# SAMV71_Xplained_Ultra_Memory.net
KiCad netlist of a schematic drawn in Altium Designer
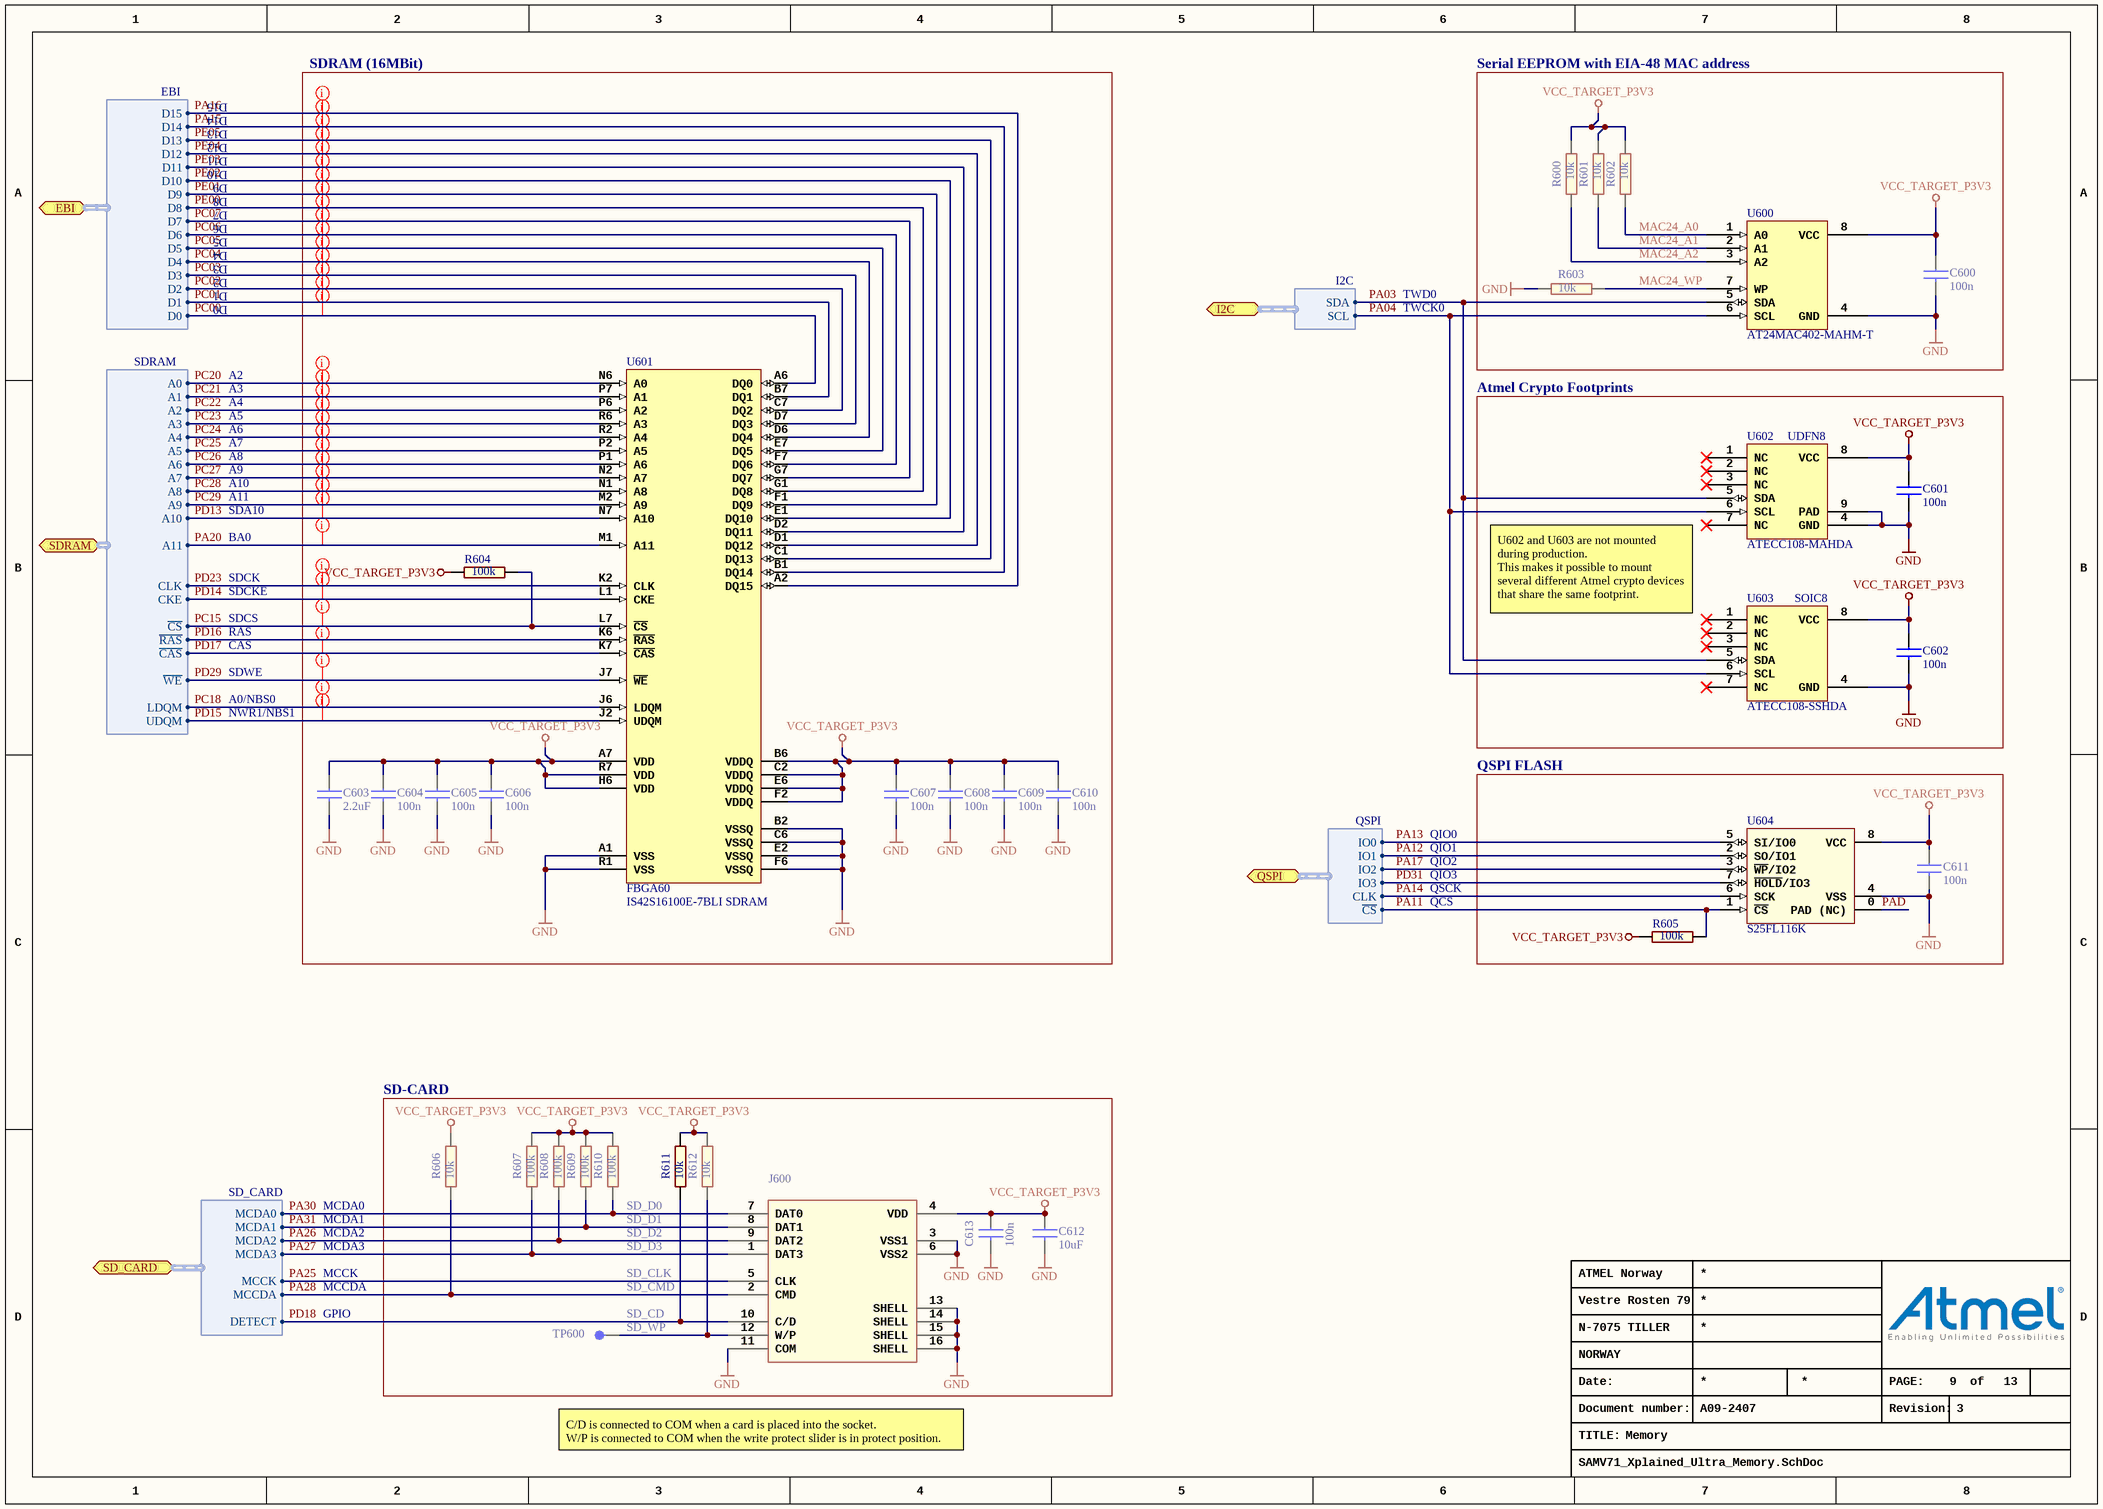
[diagram p0: SAMV71_Xplained_Ultra_Memory.SchDoc]

(export (version "E")
  (design (tool "Eeschema 10.0.6"))
  (components
    (comp (ref "C600")
      (value "100n")
      (footprint "AP1-00001")
      (description "Ceramic capacitor, SMD 0402, X7R, 16V, +/-10%")
      (fields (field (name "TOLERANCE") "16V, +/-10%") (field (name "MANUFACTURER") "Kemet"))
      (libsource (lib "AltiumDbLib") (part "CAP-NONPOL"))
    )
    (comp (ref "C601")
      (value "100n")
      (footprint "AP1-00001")
      (description "Ceramic capacitor, SMD 0402, X7R, 16V, +/-10%")
      (fields (field (name "TOLERANCE") "16V, +/-10%") (field (name "MANUFACTURER") "Kemet"))
      (libsource (lib "AltiumDbLib") (part "CAP-NONPOL"))
    )
    (comp (ref "C602")
      (value "100n")
      (footprint "AP1-00001")
      (description "Ceramic capacitor, SMD 0402, X7R, 16V, +/-10%")
      (fields (field (name "TOLERANCE") "16V, +/-10%") (field (name "MANUFACTURER") "Kemet"))
      (libsource (lib "AltiumDbLib") (part "CAP-NONPOL"))
    )
    (comp (ref "C603")
      (value "2.2uF")
      (footprint "AP1-00053")
      (description "Ceramic capacitor, SMD 0402, X5R, 6.3V, +/-20%")
      (fields (field (name "TOLERANCE") "Â±20%") (field (name "MANUFACTURER") "Kemet"))
      (libsource (lib "AltiumDbLib") (part "CAP-NONPOL"))
    )
    (comp (ref "C604")
      (value "100n")
      (footprint "AP1-00053")
      (description "Ceramic capacitor, SMD 0402, X7R, 16V, +/-10%")
      (fields (field (name "TOLERANCE") "16V, +/-10%") (field (name "MANUFACTURER") "Kemet"))
      (libsource (lib "AltiumDbLib") (part "CAP-NONPOL"))
    )
    (comp (ref "C605")
      (value "100n")
      (footprint "AP1-00053")
      (description "Ceramic capacitor, SMD 0402, X7R, 16V, +/-10%")
      (fields (field (name "TOLERANCE") "16V, +/-10%") (field (name "MANUFACTURER") "Kemet"))
      (libsource (lib "AltiumDbLib") (part "CAP-NONPOL"))
    )
    (comp (ref "C606")
      (value "100n")
      (footprint "AP1-00053")
      (description "Ceramic capacitor, SMD 0402, X7R, 16V, +/-10%")
      (fields (field (name "TOLERANCE") "16V, +/-10%") (field (name "MANUFACTURER") "Kemet"))
      (libsource (lib "AltiumDbLib") (part "CAP-NONPOL"))
    )
    (comp (ref "C607")
      (value "100n")
      (footprint "AP1-00053")
      (description "Ceramic capacitor, SMD 0402, X7R, 16V, +/-10%")
      (fields (field (name "TOLERANCE") "16V, +/-10%") (field (name "MANUFACTURER") "Kemet"))
      (libsource (lib "AltiumDbLib") (part "CAP-NONPOL"))
    )
    (comp (ref "C608")
      (value "100n")
      (footprint "AP1-00053")
      (description "Ceramic capacitor, SMD 0402, X7R, 16V, +/-10%")
      (fields (field (name "TOLERANCE") "16V, +/-10%") (field (name "MANUFACTURER") "Kemet"))
      (libsource (lib "AltiumDbLib") (part "CAP-NONPOL"))
    )
    (comp (ref "C609")
      (value "100n")
      (footprint "AP1-00053")
      (description "Ceramic capacitor, SMD 0402, X7R, 16V, +/-10%")
      (fields (field (name "TOLERANCE") "16V, +/-10%") (field (name "MANUFACTURER") "Kemet"))
      (libsource (lib "AltiumDbLib") (part "CAP-NONPOL"))
    )
    (comp (ref "C610")
      (value "100n")
      (footprint "AP1-00053")
      (description "Ceramic capacitor, SMD 0402, X7R, 16V, +/-10%")
      (fields (field (name "TOLERANCE") "16V, +/-10%") (field (name "MANUFACTURER") "Kemet"))
      (libsource (lib "AltiumDbLib") (part "CAP-NONPOL"))
    )
    (comp (ref "C611")
      (value "100n")
      (footprint "AP1-00001")
      (description "Ceramic capacitor, SMD 0402, X7R, 16V, +/-10%")
      (fields (field (name "TOLERANCE") "16V, +/-10%") (field (name "MANUFACTURER") "Kemet"))
      (libsource (lib "AltiumDbLib") (part "CAP-NONPOL"))
    )
    (comp (ref "C612")
      (value "10uF")
      (footprint "AP1-00041")
      (description "Ceramic capacitor, SMD 0805, X5R, 10V, 10 %, (de19441)")
      (fields (field (name "TOLERANCE") "10%") (field (name "MANUFACTURER") "Murata"))
      (libsource (lib "AltiumDbLib") (part "CAP-NONPOL"))
    )
    (comp (ref "C613")
      (value "100n")
      (footprint "AP1-00001")
      (description "Ceramic capacitor, SMD 0402, X7R, 16V, +/-10%")
      (fields (field (name "TOLERANCE") "16V, +/-10%") (field (name "MANUFACTURER") "Kemet"))
      (libsource (lib "AltiumDbLib") (part "CAP-NONPOL"))
    )
    (comp (ref "J600")
      (value "~")
      (footprint "AP8-00377")
      (description "SD/MMC socket, 2.7mm, push-push, SMD")
      (fields
        (field (name "MANUFACTURER") "Kyocera-elco")
        (field (name "MPN") "KYOCERA - 14 5738 009 220 859+")
      )
      (libsource (lib "AltiumDbLib") (part "SD_MMC"))
    )
    (comp (ref "R600")
      (value "10k")
      (footprint "AP2-00000")
      (description "Thick film resistor, SMD 0402, 1/16W, 1%")
      (fields (field (name "TOLERANCE") "1 %") (field (name "MANUFACTURER") "vishay"))
      (libsource (lib "AltiumDbLib") (part "R2"))
    )
    (comp (ref "R601")
      (value "10k")
      (footprint "AP2-00000")
      (description "Thick film resistor, SMD 0402, 1/16W, 1%")
      (fields (field (name "TOLERANCE") "1 %") (field (name "MANUFACTURER") "vishay"))
      (libsource (lib "AltiumDbLib") (part "R2"))
    )
    (comp (ref "R602")
      (value "10k")
      (footprint "AP2-00000")
      (description "Thick film resistor, SMD 0402, 1/16W, 1%")
      (fields (field (name "TOLERANCE") "1 %") (field (name "MANUFACTURER") "vishay"))
      (libsource (lib "AltiumDbLib") (part "R2"))
    )
    (comp (ref "R603")
      (value "10k")
      (footprint "AP2-00000")
      (description "Thick film resistor, SMD 0402, 1/16W, 1%")
      (fields (field (name "TOLERANCE") "1 %") (field (name "MANUFACTURER") "vishay"))
      (libsource (lib "") (part "R2_1"))
    )
    (comp (ref "R604")
      (value "100k")
      (footprint "AP2-00000")
      (description "Thick film resistor, SMD 0402, 1/16W, 1%")
      (fields (field (name "TOLERANCE") "1 %"))
      (libsource (lib "") (part "R2_1"))
    )
    (comp (ref "R605")
      (value "100k")
      (footprint "AP2-00000")
      (description "Thick film resistor, SMD 0402, 1/16W, 1%")
      (fields (field (name "TOLERANCE") "1 %"))
      (libsource (lib "") (part "R2_1"))
    )
    (comp (ref "R606")
      (value "10k")
      (footprint "AP2-00000")
      (description "Thick film resistor, SMD 0402, 1/16W, 1%")
      (fields (field (name "TOLERANCE") "1 %") (field (name "MANUFACTURER") "vishay"))
      (libsource (lib "AltiumDbLib") (part "R2"))
    )
    (comp (ref "R607")
      (value "100k")
      (footprint "AP2-00000")
      (description "Thick film resistor, SMD 0402, 1/16W, 1%")
      (fields (field (name "TOLERANCE") "1 %"))
      (libsource (lib "AltiumDbLib") (part "R2"))
    )
    (comp (ref "R608")
      (value "100k")
      (footprint "AP2-00000")
      (description "Thick film resistor, SMD 0402, 1/16W, 1%")
      (fields (field (name "TOLERANCE") "1 %"))
      (libsource (lib "AltiumDbLib") (part "R2"))
    )
    (comp (ref "R609")
      (value "100k")
      (footprint "AP2-00000")
      (description "Thick film resistor, SMD 0402, 1/16W, 1%")
      (fields (field (name "TOLERANCE") "1 %"))
      (libsource (lib "AltiumDbLib") (part "R2"))
    )
    (comp (ref "R610")
      (value "100k")
      (footprint "AP2-00000")
      (description "Thick film resistor, SMD 0402, 1/16W, 1%")
      (fields (field (name "TOLERANCE") "1 %"))
      (libsource (lib "AltiumDbLib") (part "R2"))
    )
    (comp (ref "R611")
      (value "10k")
      (footprint "AP2-00000")
      (description "Thick film resistor, SMD 0402, 1/16W, 1%")
      (fields (field (name "TOLERANCE") "1 %") (field (name "MANUFACTURER") "vishay"))
      (libsource (lib "AltiumDbLib") (part "R2"))
    )
    (comp (ref "R612")
      (value "10k")
      (footprint "AP2-00000")
      (description "Thick film resistor, SMD 0402, 1/16W, 1%")
      (fields (field (name "TOLERANCE") "1 %") (field (name "MANUFACTURER") "vishay"))
      (libsource (lib "AltiumDbLib") (part "R2"))
    )
    (comp (ref "TP600")
      (value "~")
      (footprint "AP8-00010")
      (description "Single SMD testpad")
      (libsource (lib "AltiumDbLib") (part "TESTPOINT"))
    )
    (comp (ref "U600")
      (value "AT24MAC402-MAHM-T")
      (footprint "AP6-00186")
      (description "2kbit I2C EEPROM, single EUI-48 MAC, 1.7-5.5V, 2x3mm UDFN (8MA2)")
      (fields (field (name "MANUFACTURER") "ATMEL"))
      (libsource (lib "AltiumDbLib") (part "AT24MAC-8PIN"))
    )
    (comp (ref "U601")
      (value "FBGA60")
      (footprint "AP6-00400")
      (description "16Mbit  SDRAM (512K Words x 16 Bits x 2 Banks), 143 MHz 3,3V")
      (fields
        (field (name "ALTIUM_VALUE") "IS42S16100E-7BLI SDRAM")
        (field (name "MANUFACTURER") "ISSI")
        (field (name "MPN") "IS42S16100E-7BLI")
      )
      (libsource (lib "AltiumDbLib") (part "IS42S16100E"))
    )
    (comp (ref "U602")
      (value "ATECC108-MAHDA")
      (footprint "AP6-00409")
      (description "Secure authentication and product validation device, EEPROM, I2C, 2.0 - 5.5V, UDFN8")
      (fields (field (name "MANUFACTURER") "ATMEL") (field (name "MPN") "ATECC108-MAHDA-T"))
      (libsource (lib "AltiumDbLib") (part "ATECC108_UDFN"))
    )
    (comp (ref "U603")
      (value "ATECC108-SSHDA")
      (footprint "AP6-00071")
      (description "Secure authentication and product validation device, EEPROM, I2C, 2.0 - 5.5V, SOIC8")
      (fields (field (name "MANUFACTURER") "ATMEL") (field (name "MPN") "ATECC108-SSHDA-T"))
      (libsource (lib "AltiumDbLib") (part "ATECC108_SOIC"))
    )
    (comp (ref "U604")
      (value "S25FL116K")
      (footprint "AP6-00402")
      (description "16 Mbit (2MB) SPI Quad I/O flash, 3.3V, 108MHz, WSON-8, industrial temperature")
      (fields (field (name "MANUFACTURER") "Spansion") (field (name "MPN") "S25FL116K0XNFI013"))
      (libsource (lib "AltiumDbLib") (part "S25FL1"))
    )
  )
  (nets
    (net (code "6") (name "/MAC24_A0") (class "Default")
      (node (ref "R602") (pin "1") (pinfunction "1_1") (pintype "passive"))
      (node (ref "U600") (pin "1") (pinfunction "A0_1") (pintype "input"))
    )
    (net (code "7") (name "/MAC24_A1") (class "Default")
      (node (ref "R601") (pin "1") (pinfunction "1_1") (pintype "passive"))
      (node (ref "U600") (pin "2") (pinfunction "A1_2") (pintype "input"))
    )
    (net (code "8") (name "/MAC24_A2") (class "Default")
      (node (ref "R600") (pin "1") (pinfunction "1_1") (pintype "passive"))
      (node (ref "U600") (pin "3") (pinfunction "A2_3") (pintype "input"))
    )
    (net (code "9") (name "/MAC24_WP") (class "Default")
      (node (ref "R603") (pin "2") (pinfunction "2_2") (pintype "passive"))
      (node (ref "U600") (pin "7") (pinfunction "WP_7") (pintype "input"))
    )
    (net (code "10") (name "/PA03") (class "Default")
      (node (ref "U600") (pin "5") (pinfunction "SDA_5") (pintype "bidirectional"))
      (node (ref "U602") (pin "5") (pinfunction "SDA_5") (pintype "bidirectional"))
      (node (ref "U603") (pin "5") (pinfunction "SDA_5") (pintype "bidirectional"))
    )
    (net (code "11") (name "/PA04") (class "Default")
      (node (ref "U600") (pin "6") (pinfunction "SCL_6") (pintype "input"))
      (node (ref "U602") (pin "6") (pinfunction "SCL_6") (pintype "input"))
      (node (ref "U603") (pin "6") (pinfunction "SCL_6") (pintype "input"))
    )
    (net (code "12") (name "/PA11") (class "Default")
      (node (ref "R605") (pin "2") (pinfunction "2_2") (pintype "passive"))
      (node (ref "U604") (pin "1") (pinfunction "~{CS}_1") (pintype "input"))
    )
    (net (code "13") (name "/PA12") (class "Default")
      (node (ref "U604") (pin "2") (pinfunction "SO/IO1_2") (pintype "bidirectional"))
    )
    (net (code "14") (name "/PA13") (class "Default")
      (node (ref "U604") (pin "5") (pinfunction "SI/IO0_5") (pintype "bidirectional"))
    )
    (net (code "15") (name "/PA14") (class "Default")
      (node (ref "U604") (pin "6") (pinfunction "SCK_6") (pintype "input"))
    )
    (net (code "16") (name "/PA15") (class "Default")
      (node (ref "U601") (pin "B1") (pinfunction "DQ14_B1") (pintype "bidirectional"))
    )
    (net (code "17") (name "/PA16") (class "Default")
      (node (ref "U601") (pin "A2") (pinfunction "DQ15_A2") (pintype "bidirectional"))
    )
    (net (code "18") (name "/PA17") (class "Default")
      (node (ref "U604") (pin "3") (pinfunction "~{WP}/IO2_3") (pintype "bidirectional"))
    )
    (net (code "19") (name "/PA20") (class "Default")
      (node (ref "U601") (pin "M1") (pinfunction "A11_M1") (pintype "input"))
    )
    (net (code "20") (name "/PA25") (class "Default")
      (node (ref "J600") (pin "5") (pinfunction "CLK_5") (pintype "passive"))
    )
    (net (code "21") (name "/PA26") (class "Default")
      (node (ref "J600") (pin "9") (pinfunction "DAT2_9") (pintype "passive"))
      (node (ref "R608") (pin "1") (pinfunction "1_1") (pintype "passive"))
    )
    (net (code "22") (name "/PA27") (class "Default")
      (node (ref "J600") (pin "1") (pinfunction "DAT3_1") (pintype "passive"))
      (node (ref "R607") (pin "1") (pinfunction "1_1") (pintype "passive"))
    )
    (net (code "23") (name "/PA28") (class "Default")
      (node (ref "J600") (pin "2") (pinfunction "CMD_2") (pintype "passive"))
      (node (ref "R606") (pin "1") (pinfunction "1_1") (pintype "passive"))
    )
    (net (code "24") (name "/PA30") (class "Default")
      (node (ref "J600") (pin "7") (pinfunction "DAT0_7") (pintype "passive"))
      (node (ref "R610") (pin "1") (pinfunction "1_1") (pintype "passive"))
    )
    (net (code "25") (name "/PA31") (class "Default")
      (node (ref "J600") (pin "8") (pinfunction "DAT1_8") (pintype "passive"))
      (node (ref "R609") (pin "1") (pinfunction "1_1") (pintype "passive"))
    )
    (net (code "26") (name "/PAD") (class "Default")
      (node (ref "U604") (pin "0") (pinfunction "PAD_(NC)_0") (pintype "power_in"))
    )
    (net (code "27") (name "/PC00") (class "Default")
      (node (ref "U601") (pin "A6") (pinfunction "DQ0_A6") (pintype "bidirectional"))
    )
    (net (code "28") (name "/PC01") (class "Default")
      (node (ref "U601") (pin "B7") (pinfunction "DQ1_B7") (pintype "bidirectional"))
    )
    (net (code "29") (name "/PC02") (class "Default")
      (node (ref "U601") (pin "C7") (pinfunction "DQ2_C7") (pintype "bidirectional"))
    )
    (net (code "30") (name "/PC03") (class "Default")
      (node (ref "U601") (pin "D7") (pinfunction "DQ3_D7") (pintype "bidirectional"))
    )
    (net (code "31") (name "/PC04") (class "Default")
      (node (ref "U601") (pin "D6") (pinfunction "DQ4_D6") (pintype "bidirectional"))
    )
    (net (code "32") (name "/PC05") (class "Default")
      (node (ref "U601") (pin "E7") (pinfunction "DQ5_E7") (pintype "bidirectional"))
    )
    (net (code "33") (name "/PC06") (class "Default")
      (node (ref "U601") (pin "F7") (pinfunction "DQ6_F7") (pintype "bidirectional"))
    )
    (net (code "34") (name "/PC07") (class "Default")
      (node (ref "U601") (pin "G7") (pinfunction "DQ7_G7") (pintype "bidirectional"))
    )
    (net (code "35") (name "/PC15") (class "Default")
      (node (ref "R604") (pin "2") (pinfunction "2_2") (pintype "passive"))
      (node (ref "U601") (pin "L7") (pinfunction "~{CS}_L7") (pintype "input"))
    )
    (net (code "36") (name "/PC18") (class "Default")
      (node (ref "U601") (pin "J6") (pinfunction "LDQM_J6") (pintype "input"))
    )
    (net (code "37") (name "/PC20") (class "Default")
      (node (ref "U601") (pin "N6") (pinfunction "A0_N6") (pintype "input"))
    )
    (net (code "38") (name "/PC21") (class "Default")
      (node (ref "U601") (pin "P7") (pinfunction "A1_P7") (pintype "input"))
    )
    (net (code "39") (name "/PC22") (class "Default")
      (node (ref "U601") (pin "P6") (pinfunction "A2_P6") (pintype "input"))
    )
    (net (code "40") (name "/PC23") (class "Default")
      (node (ref "U601") (pin "R6") (pinfunction "A3_R6") (pintype "input"))
    )
    (net (code "41") (name "/PC24") (class "Default")
      (node (ref "U601") (pin "R2") (pinfunction "A4_R2") (pintype "input"))
    )
    (net (code "42") (name "/PC25") (class "Default")
      (node (ref "U601") (pin "P2") (pinfunction "A5_P2") (pintype "input"))
    )
    (net (code "43") (name "/PC26") (class "Default")
      (node (ref "U601") (pin "P1") (pinfunction "A6_P1") (pintype "input"))
    )
    (net (code "44") (name "/PC27") (class "Default")
      (node (ref "U601") (pin "N2") (pinfunction "A7_N2") (pintype "input"))
    )
    (net (code "45") (name "/PC28") (class "Default")
      (node (ref "U601") (pin "N1") (pinfunction "A8_N1") (pintype "input"))
    )
    (net (code "46") (name "/PC29") (class "Default")
      (node (ref "U601") (pin "M2") (pinfunction "A9_M2") (pintype "input"))
    )
    (net (code "47") (name "/PD13") (class "Default")
      (node (ref "U601") (pin "N7") (pinfunction "A10_N7") (pintype "input"))
    )
    (net (code "48") (name "/PD14") (class "Default")
      (node (ref "U601") (pin "L1") (pinfunction "CKE_L1") (pintype "input"))
    )
    (net (code "49") (name "/PD15") (class "Default")
      (node (ref "U601") (pin "J2") (pinfunction "UDQM_J2") (pintype "input"))
    )
    (net (code "50") (name "/PD16") (class "Default")
      (node (ref "U601") (pin "K6") (pinfunction "~{RAS}_K6") (pintype "input"))
    )
    (net (code "51") (name "/PD17") (class "Default")
      (node (ref "U601") (pin "K7") (pinfunction "~{CAS}_K7") (pintype "input"))
    )
    (net (code "52") (name "/PD18") (class "Default")
      (node (ref "J600") (pin "10") (pinfunction "C/D_10") (pintype "passive"))
      (node (ref "R611") (pin "1") (pinfunction "1_1") (pintype "passive"))
    )
    (net (code "53") (name "/PD23") (class "Default")
      (node (ref "U601") (pin "K2") (pinfunction "CLK_K2") (pintype "input"))
    )
    (net (code "54") (name "/PD29") (class "Default")
      (node (ref "U601") (pin "J7") (pinfunction "~{WE}_J7") (pintype "input"))
    )
    (net (code "55") (name "/PD31") (class "Default")
      (node (ref "U604") (pin "7") (pinfunction "~{HOLD}/IO3_7") (pintype "bidirectional"))
    )
    (net (code "56") (name "/PE00") (class "Default")
      (node (ref "U601") (pin "G1") (pinfunction "DQ8_G1") (pintype "bidirectional"))
    )
    (net (code "57") (name "/PE01") (class "Default")
      (node (ref "U601") (pin "F1") (pinfunction "DQ9_F1") (pintype "bidirectional"))
    )
    (net (code "58") (name "/PE02") (class "Default")
      (node (ref "U601") (pin "E1") (pinfunction "DQ10_E1") (pintype "bidirectional"))
    )
    (net (code "59") (name "/PE03") (class "Default")
      (node (ref "U601") (pin "D2") (pinfunction "DQ11_D2") (pintype "bidirectional"))
    )
    (net (code "60") (name "/PE04") (class "Default")
      (node (ref "U601") (pin "D1") (pinfunction "DQ12_D1") (pintype "bidirectional"))
    )
    (net (code "61") (name "/PE05") (class "Default")
      (node (ref "U601") (pin "C1") (pinfunction "DQ13_C1") (pintype "bidirectional"))
    )
    (net (code "67") (name "GND") (class "Default")
      (node (ref "C600") (pin "2") (pinfunction "2_2") (pintype "passive"))
      (node (ref "C601") (pin "2") (pinfunction "2_2") (pintype "passive"))
      (node (ref "C602") (pin "2") (pinfunction "2_2") (pintype "passive"))
      (node (ref "C603") (pin "2") (pinfunction "2_2") (pintype "passive"))
      (node (ref "C604") (pin "2") (pinfunction "2_2") (pintype "passive"))
      (node (ref "C605") (pin "2") (pinfunction "2_2") (pintype "passive"))
      (node (ref "C606") (pin "2") (pinfunction "2_2") (pintype "passive"))
      (node (ref "C607") (pin "2") (pinfunction "2_2") (pintype "passive"))
      (node (ref "C608") (pin "2") (pinfunction "2_2") (pintype "passive"))
      (node (ref "C609") (pin "2") (pinfunction "2_2") (pintype "passive"))
      (node (ref "C610") (pin "2") (pinfunction "2_2") (pintype "passive"))
      (node (ref "C611") (pin "2") (pinfunction "2_2") (pintype "passive"))
      (node (ref "C612") (pin "2") (pinfunction "2_2") (pintype "passive"))
      (node (ref "C613") (pin "2") (pinfunction "2_2") (pintype "passive"))
      (node (ref "J600") (pin "11") (pinfunction "COM_11") (pintype "passive"))
      (node (ref "J600") (pin "13") (pinfunction "SHELL_13") (pintype "passive"))
      (node (ref "J600") (pin "14") (pinfunction "SHELL_14") (pintype "passive"))
      (node (ref "J600") (pin "15") (pinfunction "SHELL_15") (pintype "passive"))
      (node (ref "J600") (pin "16") (pinfunction "SHELL_16") (pintype "passive"))
      (node (ref "J600") (pin "3") (pinfunction "VSS1_3") (pintype "passive"))
      (node (ref "J600") (pin "6") (pinfunction "VSS2_6") (pintype "passive"))
      (node (ref "R603") (pin "1") (pinfunction "1_1") (pintype "passive"))
      (node (ref "U600") (pin "4") (pinfunction "GND_4") (pintype "power_in"))
      (node (ref "U601") (pin "A1") (pinfunction "VSS_A1") (pintype "power_in"))
      (node (ref "U601") (pin "B2") (pinfunction "VSSQ_B2") (pintype "power_in"))
      (node (ref "U601") (pin "C6") (pinfunction "VSSQ_C6") (pintype "power_in"))
      (node (ref "U601") (pin "E2") (pinfunction "VSSQ_E2") (pintype "power_in"))
      (node (ref "U601") (pin "F6") (pinfunction "VSSQ_F6") (pintype "power_in"))
      (node (ref "U601") (pin "R1") (pinfunction "VSS_R1") (pintype "power_in"))
      (node (ref "U602") (pin "4") (pinfunction "GND_4") (pintype "power_in"))
      (node (ref "U602") (pin "9") (pinfunction "PAD_9") (pintype "power_in"))
      (node (ref "U603") (pin "4") (pinfunction "GND_4") (pintype "power_in"))
      (node (ref "U604") (pin "4") (pinfunction "VSS_4") (pintype "power_in"))
    )
    (net (code "68") (name "Net-(J600-W{slash}P)") (class "Default")
      (node (ref "J600") (pin "12") (pinfunction "W/P_12") (pintype "passive"))
      (node (ref "R612") (pin "1") (pinfunction "1_1") (pintype "passive"))
      (node (ref "TP600") (pin "1") (pinfunction "1_1") (pintype "passive"))
    )
    (net (code "69") (name "VCC_TARGET_P3V3") (class "Default")
      (node (ref "C600") (pin "1") (pinfunction "1_1") (pintype "passive"))
      (node (ref "C601") (pin "1") (pinfunction "1_1") (pintype "passive"))
      (node (ref "C602") (pin "1") (pinfunction "1_1") (pintype "passive"))
      (node (ref "C603") (pin "1") (pinfunction "1_1") (pintype "passive"))
      (node (ref "C604") (pin "1") (pinfunction "1_1") (pintype "passive"))
      (node (ref "C605") (pin "1") (pinfunction "1_1") (pintype "passive"))
      (node (ref "C606") (pin "1") (pinfunction "1_1") (pintype "passive"))
      (node (ref "C607") (pin "1") (pinfunction "1_1") (pintype "passive"))
      (node (ref "C608") (pin "1") (pinfunction "1_1") (pintype "passive"))
      (node (ref "C609") (pin "1") (pinfunction "1_1") (pintype "passive"))
      (node (ref "C610") (pin "1") (pinfunction "1_1") (pintype "passive"))
      (node (ref "C611") (pin "1") (pinfunction "1_1") (pintype "passive"))
      (node (ref "C612") (pin "1") (pinfunction "1_1") (pintype "passive"))
      (node (ref "C613") (pin "1") (pinfunction "1_1") (pintype "passive"))
      (node (ref "J600") (pin "4") (pinfunction "VDD_4") (pintype "passive"))
      (node (ref "R600") (pin "2") (pinfunction "2_2") (pintype "passive"))
      (node (ref "R601") (pin "2") (pinfunction "2_2") (pintype "passive"))
      (node (ref "R602") (pin "2") (pinfunction "2_2") (pintype "passive"))
      (node (ref "R604") (pin "1") (pinfunction "1_1") (pintype "passive"))
      (node (ref "R605") (pin "1") (pinfunction "1_1") (pintype "passive"))
      (node (ref "R606") (pin "2") (pinfunction "2_2") (pintype "passive"))
      (node (ref "R607") (pin "2") (pinfunction "2_2") (pintype "passive"))
      (node (ref "R608") (pin "2") (pinfunction "2_2") (pintype "passive"))
      (node (ref "R609") (pin "2") (pinfunction "2_2") (pintype "passive"))
      (node (ref "R610") (pin "2") (pinfunction "2_2") (pintype "passive"))
      (node (ref "R611") (pin "2") (pinfunction "2_2") (pintype "passive"))
      (node (ref "R612") (pin "2") (pinfunction "2_2") (pintype "passive"))
      (node (ref "U600") (pin "8") (pinfunction "VCC_8") (pintype "power_in"))
      (node (ref "U601") (pin "A7") (pinfunction "VDD_A7") (pintype "power_in"))
      (node (ref "U601") (pin "B6") (pinfunction "VDDQ_B6") (pintype "power_in"))
      (node (ref "U601") (pin "C2") (pinfunction "VDDQ_C2") (pintype "power_in"))
      (node (ref "U601") (pin "E6") (pinfunction "VDDQ_E6") (pintype "power_in"))
      (node (ref "U601") (pin "F2") (pinfunction "VDDQ_F2") (pintype "power_in"))
      (node (ref "U601") (pin "H6") (pinfunction "VDD_H6") (pintype "power_in"))
      (node (ref "U601") (pin "R7") (pinfunction "VDD_R7") (pintype "power_in"))
      (node (ref "U602") (pin "8") (pinfunction "VCC_8") (pintype "power_in"))
      (node (ref "U603") (pin "8") (pinfunction "VCC_8") (pintype "power_in"))
      (node (ref "U604") (pin "8") (pinfunction "VCC_8") (pintype "power_in"))
    )
    (net (code "70") (name "unconnected-(U602-NC-Pad1)") (class "Default")
      (node (ref "U602") (pin "1") (pinfunction "NC_1") (pintype "passive+no_connect"))
    )
    (net (code "71") (name "unconnected-(U602-NC-Pad2)") (class "Default")
      (node (ref "U602") (pin "2") (pinfunction "NC_2") (pintype "passive+no_connect"))
    )
    (net (code "72") (name "unconnected-(U602-NC-Pad3)") (class "Default")
      (node (ref "U602") (pin "3") (pinfunction "NC_3") (pintype "passive+no_connect"))
    )
    (net (code "73") (name "unconnected-(U602-NC-Pad7)") (class "Default")
      (node (ref "U602") (pin "7") (pinfunction "NC_7") (pintype "passive+no_connect"))
    )
    (net (code "74") (name "unconnected-(U603-NC-Pad1)") (class "Default")
      (node (ref "U603") (pin "1") (pinfunction "NC_1") (pintype "passive+no_connect"))
    )
    (net (code "75") (name "unconnected-(U603-NC-Pad2)") (class "Default")
      (node (ref "U603") (pin "2") (pinfunction "NC_2") (pintype "passive+no_connect"))
    )
    (net (code "76") (name "unconnected-(U603-NC-Pad3)") (class "Default")
      (node (ref "U603") (pin "3") (pinfunction "NC_3") (pintype "passive+no_connect"))
    )
    (net (code "77") (name "unconnected-(U603-NC-Pad7)") (class "Default")
      (node (ref "U603") (pin "7") (pinfunction "NC_7") (pintype "passive+no_connect"))
    )
  )
)
